# Half_Bridge.net
KiCad netlist of a schematic drawn in Altium Designer
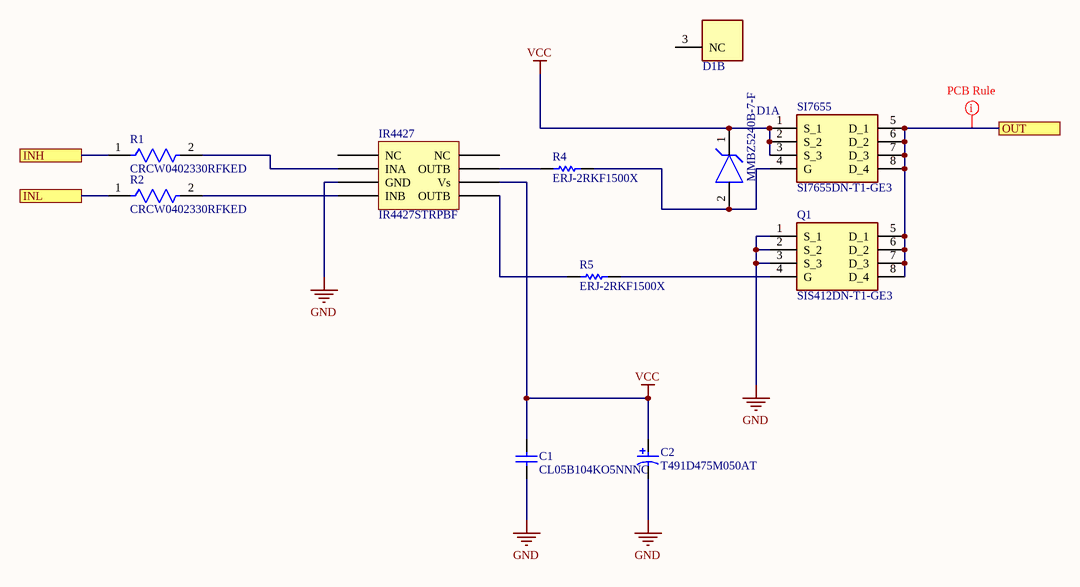
[diagram p0: Half_Bridge.SchDoc]

(export (version "E")
  (design (tool "Eeschema 10.0.6"))
  (components
    (comp (ref "C1")
      (value "CL05B104KO5NNNC")
      (footprint "CAPC1050X55X23ML05T13")
      (description "Chip Capacitor, 100 nF, +/- 10%, 16 V, -55 to 125 degC, 0402 (1005 Metric), RoHS, Tape and Reel")
      (fields (field (name "MANUFACTURER") "Samsung Electro-Mechanics"))
      (libsource (lib "Altium Content Vault") (part "CAP-NP-2"))
    )
    (comp (ref "C2")
      (value "T491D475M050AT")
      (footprint "KEMT-T491-D_L")
      (fields (field (name "VOLTAGE") "50VDC") (field (name "MANUFACTURER") "Kemet"))
      (libsource (lib "Altium Content Vault") (part "CAP-P-2"))
    )
    (comp (ref "D1")
      (value "MMBZ5240B-7-F")
      (footprint "Diodes_SOT23_0")
      (libsource (lib "Diode_Diodes_MMBZ5240B-7-F_eec") (part "MMBZ5240B-7-F"))
    )
    (comp (ref "IR4427")
      (value "IR4427STRPBF")
      (footprint "IR4427-PCB")
      (description "IC DRIVER DUAL LOW SIDE 8-DIP")
      (libsource (lib "Schlib1") (part "IR4427"))
    )
    (comp (ref "Q1")
      (value "SIS412DN-T1-GE3")
      (footprint "POWERPAK-1212-8")
      (description "MOSFET (N-Channel)")
      (fields (field (name "MOUSER2 PART NUMBER") "781-SIS412DN-T1-GE3"))
      (libsource (lib "SamacSys") (part "SIS412DN-T1-GE3"))
    )
    (comp (ref "R1")
      (value "CRCW0402330RFKED")
      (footprint "FP-CRCW0402-e3-MFG")
      (description "RES Thick Film, 330Ω, 1%, 0.063W, 100ppm/°C, 0402")
      (fields (field (name "TOLERANCE") "1%"))
      (libsource (lib "Altium Content Vault") (part "1029c3af85768c4190bb7ad29bc67b5"))
    )
    (comp (ref "R2")
      (value "CRCW0402330RFKED")
      (footprint "FP-CRCW0402-e3-MFG")
      (description "RES Thick Film, 330Ω, 1%, 0.063W, 100ppm/°C, 0402")
      (fields (field (name "TOLERANCE") "1%"))
      (libsource (lib "Altium Content Vault") (part "1029c3af85768c4190bb7ad29bc67b5"))
    )
    (comp (ref "R4")
      (value "ERJ-2RKF1500X")
      (footprint "RESC1005X40X25NL05T05")
      (fields (field (name "MANUFACTURER") "Panasonic"))
      (libsource (lib "Altium Content Vault") (part "RES"))
    )
    (comp (ref "R5")
      (value "ERJ-2RKF1500X")
      (footprint "RESC1005X40X25NL05T05")
      (fields (field (name "MANUFACTURER") "Panasonic"))
      (libsource (lib "Altium Content Vault") (part "RES"))
    )
    (comp (ref "SI7655")
      (value "SI7655DN-T1-GE3")
      (footprint "SIS862DNT1GE3")
      (description "MOSFET (P-Channel)")
      (fields (field (name "MOUSER PART NUMBER") "78-SI7655DN-T1-GE3"))
      (libsource (lib "SamacSys") (part "SI7655DN-T1-GE3"))
    )
  )
  (nets
    (net (code "1") (name "/INH") (class "Default")
      (node (ref "R1") (pin "1") (pinfunction "1_1") (pintype "passive"))
    )
    (net (code "2") (name "/INL") (class "Default")
      (node (ref "R2") (pin "1") (pinfunction "1_1") (pintype "passive"))
    )
    (net (code "3") (name "/OUT") (class "Default")
      (node (ref "Q1") (pin "5") (pinfunction "D_1_5") (pintype "passive"))
      (node (ref "Q1") (pin "6") (pinfunction "D_2_6") (pintype "passive"))
      (node (ref "Q1") (pin "7") (pinfunction "D_3_7") (pintype "passive"))
      (node (ref "Q1") (pin "8") (pinfunction "D_4_8") (pintype "passive"))
      (node (ref "SI7655") (pin "5") (pinfunction "D_1_5") (pintype "passive"))
      (node (ref "SI7655") (pin "6") (pinfunction "D_2_6") (pintype "passive"))
      (node (ref "SI7655") (pin "7") (pinfunction "D_3_7") (pintype "passive"))
      (node (ref "SI7655") (pin "8") (pinfunction "D_4_8") (pintype "passive"))
    )
    (net (code "4") (name "GND") (class "Default")
      (node (ref "C1") (pin "1") (pinfunction "1_1") (pintype "passive"))
      (node (ref "C2") (pin "2") (pinfunction "2_2") (pintype "passive"))
      (node (ref "IR4427") (pin "3") (pinfunction "GND_3") (pintype "passive"))
      (node (ref "Q1") (pin "1") (pinfunction "S_1_1") (pintype "passive"))
      (node (ref "Q1") (pin "2") (pinfunction "S_2_2") (pintype "passive"))
      (node (ref "Q1") (pin "3") (pinfunction "S_3_3") (pintype "passive"))
    )
    (net (code "5") (name "Net-(D1A-A)") (class "Default")
      (node (ref "D1") (pin "2") (pinfunction "A_2") (pintype "passive"))
      (node (ref "R4") (pin "2") (pinfunction "2_2") (pintype "passive"))
      (node (ref "SI7655") (pin "4") (pinfunction "G_4") (pintype "passive"))
    )
    (net (code "6") (name "Net-(IR4427-INA)") (class "Default")
      (node (ref "IR4427") (pin "2") (pinfunction "INA_2") (pintype "passive"))
      (node (ref "R1") (pin "2") (pinfunction "2_2") (pintype "passive"))
    )
    (net (code "7") (name "Net-(IR4427-INB)") (class "Default")
      (node (ref "IR4427") (pin "4") (pinfunction "INB_4") (pintype "passive"))
      (node (ref "R2") (pin "2") (pinfunction "2_2") (pintype "passive"))
    )
    (net (code "8") (name "Net-(IR4427-OUTB-Pad5)") (class "Default")
      (node (ref "IR4427") (pin "5") (pinfunction "OUTB_5") (pintype "passive"))
      (node (ref "R5") (pin "1") (pinfunction "1_1") (pintype "passive"))
    )
    (net (code "9") (name "Net-(IR4427-OUTB-Pad7)") (class "Default")
      (node (ref "IR4427") (pin "7") (pinfunction "OUTB_7") (pintype "passive"))
      (node (ref "R4") (pin "1") (pinfunction "1_1") (pintype "passive"))
    )
    (net (code "10") (name "Net-(Q1-G)") (class "Default")
      (node (ref "Q1") (pin "4") (pinfunction "G_4") (pintype "passive"))
      (node (ref "R5") (pin "2") (pinfunction "2_2") (pintype "passive"))
    )
    (net (code "11") (name "VCC") (class "Default")
      (node (ref "C1") (pin "2") (pinfunction "2_2") (pintype "passive"))
      (node (ref "C2") (pin "1") (pinfunction "1_1") (pintype "passive"))
      (node (ref "D1") (pin "1") (pinfunction "C_1") (pintype "passive"))
      (node (ref "IR4427") (pin "6") (pinfunction "Vs_6") (pintype "passive"))
      (node (ref "SI7655") (pin "1") (pinfunction "S_1_1") (pintype "passive"))
      (node (ref "SI7655") (pin "2") (pinfunction "S_2_2") (pintype "passive"))
      (node (ref "SI7655") (pin "3") (pinfunction "S_3_3") (pintype "passive"))
    )
    (net (code "12") (name "unconnected-(D1B-NC-Pad3)") (class "Default")
      (node (ref "D1") (pin "3") (pinfunction "NC_3") (pintype "passive"))
    )
    (net (code "13") (name "unconnected-(IR4427-NC-Pad1)") (class "Default")
      (node (ref "IR4427") (pin "1") (pinfunction "NC_1") (pintype "passive"))
    )
    (net (code "14") (name "unconnected-(IR4427-NC-Pad8)") (class "Default")
      (node (ref "IR4427") (pin "8") (pinfunction "NC_8") (pintype "passive"))
    )
  )
)
